# Motorisation.net
KiCad netlist of a schematic drawn in Altium Designer
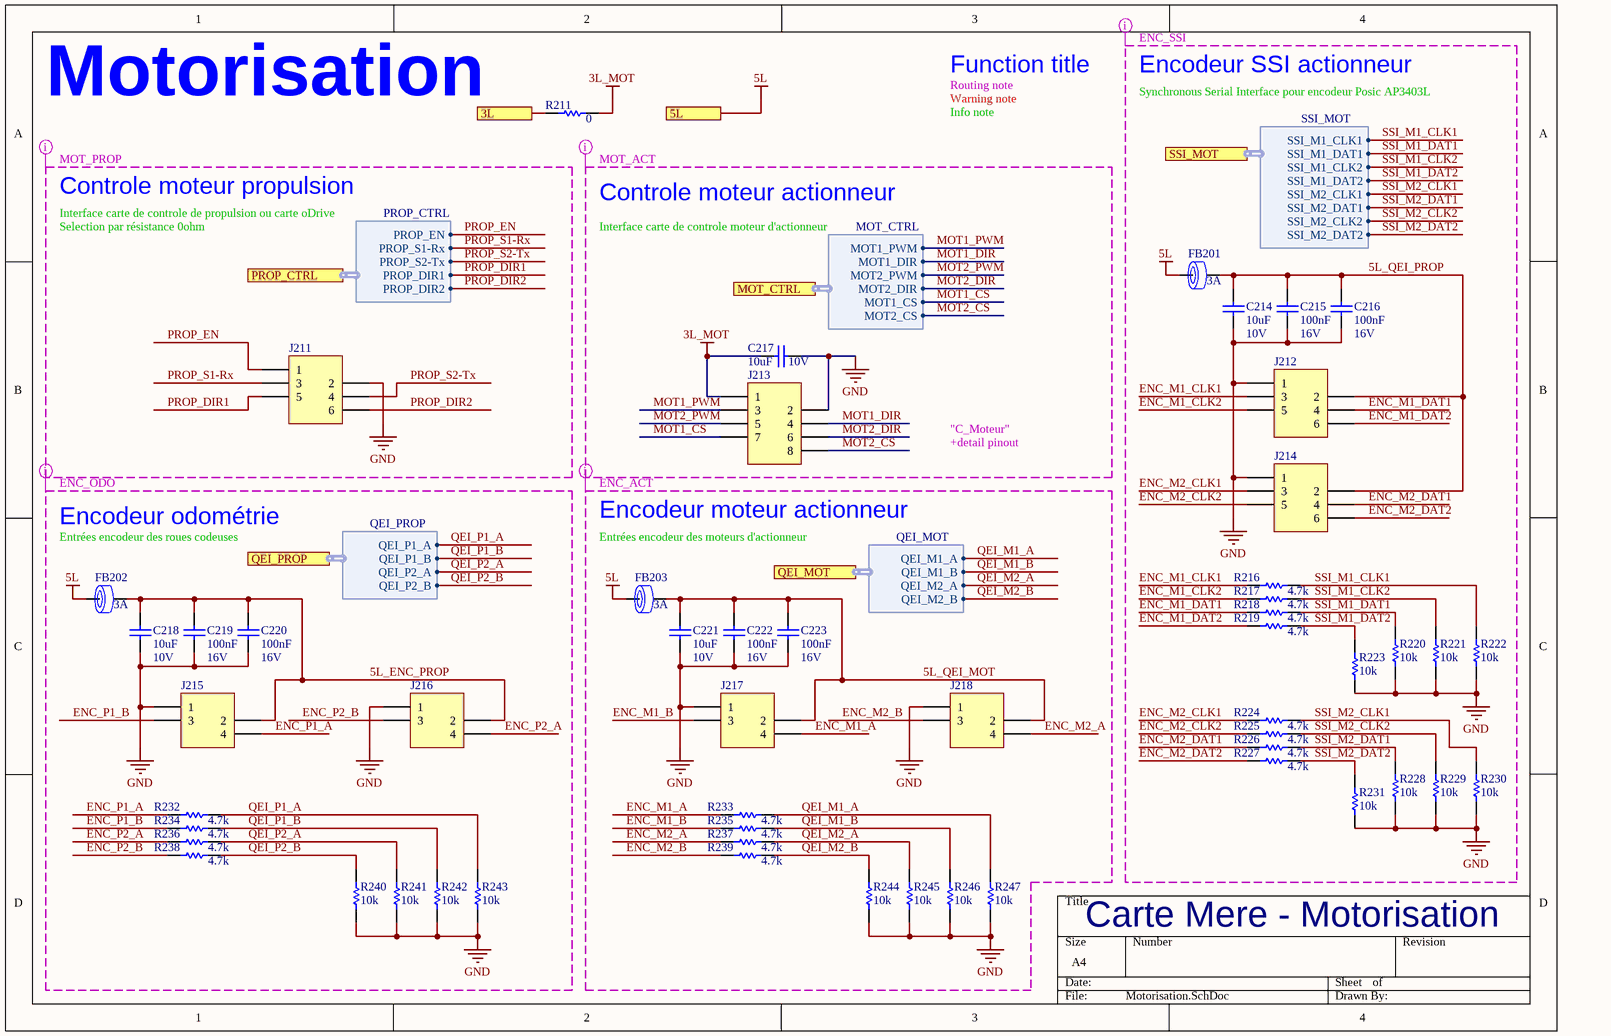
[diagram p0: Motorisation.SchDoc]

(export (version "E")
  (design (tool "Eeschema 10.0.6"))
  (components
    (comp (ref "C214")
      (value "10uF")
      (footprint "WCAP-CSGP_0805, 2x1.25x1.25")
      (description "CAP CER 10uF 10V X7R 0805")
      (fields
        (field (name "MANUFACTURER") "Wurth Elektronik")
        (field (name "MANUFACTURER PART NUMBER") "885012207026")
        (field (name "RATEDVOLTAGE") "10V")
      )
      (libsource (lib "Condensateur") (part "WCAP-CSGP, 885012207026"))
    )
    (comp (ref "C215")
      (value "100nF")
      (footprint "WCAP-CSGP_0402, 1x0.5x0.5")
      (description "CAP CER 100nF 16V X7R 0402")
      (fields
        (field (name "MANUFACTURER") "Wurth Elektronik")
        (field (name "MANUFACTURER PART NUMBER") "885012205037")
        (field (name "RATEDVOLTAGE") "16V")
      )
      (libsource (lib "Condensateur") (part "WCAP-CSGP, 885012205037"))
    )
    (comp (ref "C216")
      (value "100nF")
      (footprint "WCAP-CSGP_0402, 1x0.5x0.5")
      (description "CAP CER 100nF 16V X7R 0402")
      (fields
        (field (name "MANUFACTURER") "Wurth Elektronik")
        (field (name "MANUFACTURER PART NUMBER") "885012205037")
        (field (name "RATEDVOLTAGE") "16V")
      )
      (libsource (lib "Condensateur") (part "WCAP-CSGP, 885012205037"))
    )
    (comp (ref "C217")
      (value "10uF")
      (footprint "WCAP-CSGP_0805, 2x1.25x1.25")
      (description "CAP CER 10uF 10V X7R 0805")
      (fields
        (field (name "MANUFACTURER") "Wurth Elektronik")
        (field (name "MANUFACTURER PART NUMBER") "885012207026")
        (field (name "RATEDVOLTAGE") "10V")
      )
      (libsource (lib "Condensateur") (part "WCAP-CSGP, 885012207026"))
    )
    (comp (ref "C218")
      (value "10uF")
      (footprint "WCAP-CSGP_0805, 2x1.25x1.25")
      (description "CAP CER 10uF 10V X7R 0805")
      (fields
        (field (name "MANUFACTURER") "Wurth Elektronik")
        (field (name "MANUFACTURER PART NUMBER") "885012207026")
        (field (name "RATEDVOLTAGE") "10V")
      )
      (libsource (lib "Condensateur") (part "WCAP-CSGP, 885012207026"))
    )
    (comp (ref "C219")
      (value "100nF")
      (footprint "WCAP-CSGP_0402, 1x0.5x0.5")
      (description "CAP CER 100nF 16V X7R 0402")
      (fields
        (field (name "MANUFACTURER") "Wurth Elektronik")
        (field (name "MANUFACTURER PART NUMBER") "885012205037")
        (field (name "RATEDVOLTAGE") "16V")
      )
      (libsource (lib "Condensateur") (part "WCAP-CSGP, 885012205037"))
    )
    (comp (ref "C220")
      (value "100nF")
      (footprint "WCAP-CSGP_0402, 1x0.5x0.5")
      (description "CAP CER 100nF 16V X7R 0402")
      (fields
        (field (name "MANUFACTURER") "Wurth Elektronik")
        (field (name "MANUFACTURER PART NUMBER") "885012205037")
        (field (name "RATEDVOLTAGE") "16V")
      )
      (libsource (lib "Condensateur") (part "WCAP-CSGP, 885012205037"))
    )
    (comp (ref "C221")
      (value "10uF")
      (footprint "WCAP-CSGP_0805, 2x1.25x1.25")
      (description "CAP CER 10uF 10V X7R 0805")
      (fields
        (field (name "MANUFACTURER") "Wurth Elektronik")
        (field (name "MANUFACTURER PART NUMBER") "885012207026")
        (field (name "RATEDVOLTAGE") "10V")
      )
      (libsource (lib "Condensateur") (part "WCAP-CSGP, 885012207026"))
    )
    (comp (ref "C222")
      (value "100nF")
      (footprint "WCAP-CSGP_0402, 1x0.5x0.5")
      (description "CAP CER 100nF 16V X7R 0402")
      (fields
        (field (name "MANUFACTURER") "Wurth Elektronik")
        (field (name "MANUFACTURER PART NUMBER") "885012205037")
        (field (name "RATEDVOLTAGE") "16V")
      )
      (libsource (lib "Condensateur") (part "WCAP-CSGP, 885012205037"))
    )
    (comp (ref "C223")
      (value "100nF")
      (footprint "WCAP-CSGP_0402, 1x0.5x0.5")
      (description "CAP CER 100nF 16V X7R 0402")
      (fields
        (field (name "MANUFACTURER") "Wurth Elektronik")
        (field (name "MANUFACTURER PART NUMBER") "885012205037")
        (field (name "RATEDVOLTAGE") "16V")
      )
      (libsource (lib "Condensateur") (part "WCAP-CSGP, 885012205037"))
    )
    (comp (ref "FB201")
      (value "742792023")
      (footprint "WE-CBF_0805_High Current")
      (description "Ferrite Bead 120ohm 0805 3A")
      (fields (field (name "MANUFACTURER") "Wurth Elektronik") (field (name "RATEDCURRENT") "3A"))
      (libsource (lib "Inductance") (part "WE-CBF, 742792023"))
    )
    (comp (ref "FB202")
      (value "742792023")
      (footprint "WE-CBF_0805_High Current")
      (description "Ferrite Bead 120ohm 0805 3A")
      (fields (field (name "MANUFACTURER") "Wurth Elektronik") (field (name "RATEDCURRENT") "3A"))
      (libsource (lib "Inductance") (part "WE-CBF, 742792023"))
    )
    (comp (ref "FB203")
      (value "742792023")
      (footprint "WE-CBF_0805_High Current")
      (description "Ferrite Bead 120ohm 0805 3A")
      (fields (field (name "MANUFACTURER") "Wurth Elektronik") (field (name "RATEDCURRENT") "3A"))
      (libsource (lib "Inductance") (part "WE-CBF, 742792023"))
    )
    (comp (ref "J211")
      (value "690367280676")
      (footprint "690367280676")
      (description "WR-MM 6p Female SMT Connector with Polarization")
      (fields (field (name "MANUFACTURER") "Wurth Electronics Inc."))
      (libsource (lib "Connecteurs") (part "690367280676"))
    )
    (comp (ref "J212")
      (value "690367280676")
      (footprint "690367280676")
      (description "WR-MM 6p Female SMT Connector with Polarization")
      (fields (field (name "MANUFACTURER") "Wurth Electronics Inc."))
      (libsource (lib "Connecteurs") (part "690367280676"))
    )
    (comp (ref "J213")
      (value "690367280876")
      (footprint "690367280876")
      (description "WR-MM 8p Female SMT Connector with Polarization")
      (fields (field (name "MANUFACTURER") "Wurth Electronics Inc."))
      (libsource (lib "Connecteurs") (part "690367280876"))
    )
    (comp (ref "J214")
      (value "690367280676")
      (footprint "690367280676")
      (description "WR-MM 6p Female SMT Connector with Polarization")
      (fields (field (name "MANUFACTURER") "Wurth Electronics Inc."))
      (libsource (lib "Connecteurs") (part "690367280676"))
    )
    (comp (ref "J215")
      (value "690367280476")
      (footprint "690367280476")
      (description "WR-MM 4p Female SMT Connector with Polarization")
      (fields (field (name "MANUFACTURER") "Wurth Electronics Inc."))
      (libsource (lib "Connecteurs") (part "690367280476"))
    )
    (comp (ref "J216")
      (value "690367280476")
      (footprint "690367280476")
      (description "WR-MM 4p Female SMT Connector with Polarization")
      (fields (field (name "MANUFACTURER") "Wurth Electronics Inc."))
      (libsource (lib "Connecteurs") (part "690367280476"))
    )
    (comp (ref "J217")
      (value "690367280476")
      (footprint "690367280476")
      (description "WR-MM 4p Female SMT Connector with Polarization")
      (fields (field (name "MANUFACTURER") "Wurth Electronics Inc."))
      (libsource (lib "Connecteurs") (part "690367280476"))
    )
    (comp (ref "J218")
      (value "690367280476")
      (footprint "690367280476")
      (description "WR-MM 4p Female SMT Connector with Polarization")
      (fields (field (name "MANUFACTURER") "Wurth Electronics Inc."))
      (libsource (lib "Connecteurs") (part "690367280476"))
    )
    (comp (ref "R211")
      (value "0")
      (footprint "RESC1608X06N")
      (description "RES SMD 0 OHM 1% 1/10W 0603")
      (fields
        (field (name "MANUFACTURER") "Yageo")
        (field (name "MANUFACTURER PART NUMBER") "RC0603FR-070RL")
      )
      (libsource (lib "Resistance") (part "RC0603FR-070RL"))
    )
    (comp (ref "R216")
      (value "4.7k")
      (footprint "RESC1005X04N")
      (description "RES SMD 4K7 OHM 1% 1/16W 0402")
      (fields (field (name "POWER") "63mW") (field (name "MANUFACTURER") "Yageo"))
      (libsource (lib "Resistance") (part "RC0402FR-074K7L"))
    )
    (comp (ref "R217")
      (value "4.7k")
      (footprint "RESC1005X04N")
      (description "RES SMD 4K7 OHM 1% 1/16W 0402")
      (fields (field (name "POWER") "63mW") (field (name "MANUFACTURER") "Yageo"))
      (libsource (lib "Resistance") (part "RC0402FR-074K7L"))
    )
    (comp (ref "R218")
      (value "4.7k")
      (footprint "RESC1005X04N")
      (description "RES SMD 4K7 OHM 1% 1/16W 0402")
      (fields (field (name "POWER") "63mW") (field (name "MANUFACTURER") "Yageo"))
      (libsource (lib "Resistance") (part "RC0402FR-074K7L"))
    )
    (comp (ref "R219")
      (value "4.7k")
      (footprint "RESC1005X04N")
      (description "RES SMD 4K7 OHM 1% 1/16W 0402")
      (fields (field (name "POWER") "63mW") (field (name "MANUFACTURER") "Yageo"))
      (libsource (lib "Resistance") (part "RC0402FR-074K7L"))
    )
    (comp (ref "R220")
      (value "10k")
      (footprint "RESC1005X04N")
      (description "RES SMD 10K OHM 1% 1/16W 0402")
      (fields (field (name "POWER") "63mW") (field (name "MANUFACTURER") "Yageo"))
      (libsource (lib "Resistance") (part "RC0402FR-0710KL"))
    )
    (comp (ref "R221")
      (value "10k")
      (footprint "RESC1005X04N")
      (description "RES SMD 10K OHM 1% 1/16W 0402")
      (fields (field (name "POWER") "63mW") (field (name "MANUFACTURER") "Yageo"))
      (libsource (lib "Resistance") (part "RC0402FR-0710KL"))
    )
    (comp (ref "R222")
      (value "10k")
      (footprint "RESC1005X04N")
      (description "RES SMD 10K OHM 1% 1/16W 0402")
      (fields (field (name "POWER") "63mW") (field (name "MANUFACTURER") "Yageo"))
      (libsource (lib "Resistance") (part "RC0402FR-0710KL"))
    )
    (comp (ref "R223")
      (value "10k")
      (footprint "RESC1005X04N")
      (description "RES SMD 10K OHM 1% 1/16W 0402")
      (fields (field (name "POWER") "63mW") (field (name "MANUFACTURER") "Yageo"))
      (libsource (lib "Resistance") (part "RC0402FR-0710KL"))
    )
    (comp (ref "R224")
      (value "4.7k")
      (footprint "RESC1005X04N")
      (description "RES SMD 4K7 OHM 1% 1/16W 0402")
      (fields (field (name "POWER") "63mW") (field (name "MANUFACTURER") "Yageo"))
      (libsource (lib "Resistance") (part "RC0402FR-074K7L"))
    )
    (comp (ref "R225")
      (value "4.7k")
      (footprint "RESC1005X04N")
      (description "RES SMD 4K7 OHM 1% 1/16W 0402")
      (fields (field (name "POWER") "63mW") (field (name "MANUFACTURER") "Yageo"))
      (libsource (lib "Resistance") (part "RC0402FR-074K7L"))
    )
    (comp (ref "R226")
      (value "4.7k")
      (footprint "RESC1005X04N")
      (description "RES SMD 4K7 OHM 1% 1/16W 0402")
      (fields (field (name "POWER") "63mW") (field (name "MANUFACTURER") "Yageo"))
      (libsource (lib "Resistance") (part "RC0402FR-074K7L"))
    )
    (comp (ref "R227")
      (value "4.7k")
      (footprint "RESC1005X04N")
      (description "RES SMD 4K7 OHM 1% 1/16W 0402")
      (fields (field (name "POWER") "63mW") (field (name "MANUFACTURER") "Yageo"))
      (libsource (lib "Resistance") (part "RC0402FR-074K7L"))
    )
    (comp (ref "R228")
      (value "10k")
      (footprint "RESC1005X04N")
      (description "RES SMD 10K OHM 1% 1/16W 0402")
      (fields (field (name "POWER") "63mW") (field (name "MANUFACTURER") "Yageo"))
      (libsource (lib "Resistance") (part "RC0402FR-0710KL"))
    )
    (comp (ref "R229")
      (value "10k")
      (footprint "RESC1005X04N")
      (description "RES SMD 10K OHM 1% 1/16W 0402")
      (fields (field (name "POWER") "63mW") (field (name "MANUFACTURER") "Yageo"))
      (libsource (lib "Resistance") (part "RC0402FR-0710KL"))
    )
    (comp (ref "R230")
      (value "10k")
      (footprint "RESC1005X04N")
      (description "RES SMD 10K OHM 1% 1/16W 0402")
      (fields (field (name "POWER") "63mW") (field (name "MANUFACTURER") "Yageo"))
      (libsource (lib "Resistance") (part "RC0402FR-0710KL"))
    )
    (comp (ref "R231")
      (value "10k")
      (footprint "RESC1005X04N")
      (description "RES SMD 10K OHM 1% 1/16W 0402")
      (fields (field (name "POWER") "63mW") (field (name "MANUFACTURER") "Yageo"))
      (libsource (lib "Resistance") (part "RC0402FR-0710KL"))
    )
    (comp (ref "R232")
      (value "4.7k")
      (footprint "RESC1005X04N")
      (description "RES SMD 4K7 OHM 1% 1/16W 0402")
      (fields (field (name "POWER") "63mW") (field (name "MANUFACTURER") "Yageo"))
      (libsource (lib "Resistance") (part "RC0402FR-074K7L"))
    )
    (comp (ref "R233")
      (value "4.7k")
      (footprint "RESC1005X04N")
      (description "RES SMD 4K7 OHM 1% 1/16W 0402")
      (fields (field (name "POWER") "63mW") (field (name "MANUFACTURER") "Yageo"))
      (libsource (lib "Resistance") (part "RC0402FR-074K7L"))
    )
    (comp (ref "R234")
      (value "4.7k")
      (footprint "RESC1005X04N")
      (description "RES SMD 4K7 OHM 1% 1/16W 0402")
      (fields (field (name "POWER") "63mW") (field (name "MANUFACTURER") "Yageo"))
      (libsource (lib "Resistance") (part "RC0402FR-074K7L"))
    )
    (comp (ref "R235")
      (value "4.7k")
      (footprint "RESC1005X04N")
      (description "RES SMD 4K7 OHM 1% 1/16W 0402")
      (fields (field (name "POWER") "63mW") (field (name "MANUFACTURER") "Yageo"))
      (libsource (lib "Resistance") (part "RC0402FR-074K7L"))
    )
    (comp (ref "R236")
      (value "4.7k")
      (footprint "RESC1005X04N")
      (description "RES SMD 4K7 OHM 1% 1/16W 0402")
      (fields (field (name "POWER") "63mW") (field (name "MANUFACTURER") "Yageo"))
      (libsource (lib "Resistance") (part "RC0402FR-074K7L"))
    )
    (comp (ref "R237")
      (value "4.7k")
      (footprint "RESC1005X04N")
      (description "RES SMD 4K7 OHM 1% 1/16W 0402")
      (fields (field (name "POWER") "63mW") (field (name "MANUFACTURER") "Yageo"))
      (libsource (lib "Resistance") (part "RC0402FR-074K7L"))
    )
    (comp (ref "R238")
      (value "4.7k")
      (footprint "RESC1005X04N")
      (description "RES SMD 4K7 OHM 1% 1/16W 0402")
      (fields (field (name "POWER") "63mW") (field (name "MANUFACTURER") "Yageo"))
      (libsource (lib "Resistance") (part "RC0402FR-074K7L"))
    )
    (comp (ref "R239")
      (value "4.7k")
      (footprint "RESC1005X04N")
      (description "RES SMD 4K7 OHM 1% 1/16W 0402")
      (fields (field (name "POWER") "63mW") (field (name "MANUFACTURER") "Yageo"))
      (libsource (lib "Resistance") (part "RC0402FR-074K7L"))
    )
    (comp (ref "R240")
      (value "10k")
      (footprint "RESC1005X04N")
      (description "RES SMD 10K OHM 1% 1/16W 0402")
      (fields (field (name "POWER") "63mW") (field (name "MANUFACTURER") "Yageo"))
      (libsource (lib "Resistance") (part "RC0402FR-0710KL"))
    )
    (comp (ref "R241")
      (value "10k")
      (footprint "RESC1005X04N")
      (description "RES SMD 10K OHM 1% 1/16W 0402")
      (fields (field (name "POWER") "63mW") (field (name "MANUFACTURER") "Yageo"))
      (libsource (lib "Resistance") (part "RC0402FR-0710KL"))
    )
    (comp (ref "R242")
      (value "10k")
      (footprint "RESC1005X04N")
      (description "RES SMD 10K OHM 1% 1/16W 0402")
      (fields (field (name "POWER") "63mW") (field (name "MANUFACTURER") "Yageo"))
      (libsource (lib "Resistance") (part "RC0402FR-0710KL"))
    )
    (comp (ref "R243")
      (value "10k")
      (footprint "RESC1005X04N")
      (description "RES SMD 10K OHM 1% 1/16W 0402")
      (fields (field (name "POWER") "63mW") (field (name "MANUFACTURER") "Yageo"))
      (libsource (lib "Resistance") (part "RC0402FR-0710KL"))
    )
    (comp (ref "R244")
      (value "10k")
      (footprint "RESC1005X04N")
      (description "RES SMD 10K OHM 1% 1/16W 0402")
      (fields (field (name "POWER") "63mW") (field (name "MANUFACTURER") "Yageo"))
      (libsource (lib "Resistance") (part "RC0402FR-0710KL"))
    )
    (comp (ref "R245")
      (value "10k")
      (footprint "RESC1005X04N")
      (description "RES SMD 10K OHM 1% 1/16W 0402")
      (fields (field (name "POWER") "63mW") (field (name "MANUFACTURER") "Yageo"))
      (libsource (lib "Resistance") (part "RC0402FR-0710KL"))
    )
    (comp (ref "R246")
      (value "10k")
      (footprint "RESC1005X04N")
      (description "RES SMD 10K OHM 1% 1/16W 0402")
      (fields (field (name "POWER") "63mW") (field (name "MANUFACTURER") "Yageo"))
      (libsource (lib "Resistance") (part "RC0402FR-0710KL"))
    )
    (comp (ref "R247")
      (value "10k")
      (footprint "RESC1005X04N")
      (description "RES SMD 10K OHM 1% 1/16W 0402")
      (fields (field (name "POWER") "63mW") (field (name "MANUFACTURER") "Yageo"))
      (libsource (lib "Resistance") (part "RC0402FR-0710KL"))
    )
  )
  (nets
    (net (code "6") (name "/3L") (class "Default")
      (node (ref "R211") (pin "1") (pinfunction "1_1") (pintype "passive"))
    )
    (net (code "7") (name "/5L_ENC_PROP") (class "Default")
      (node (ref "C218") (pin "1") (pinfunction "1_1") (pintype "passive"))
      (node (ref "C219") (pin "1") (pinfunction "1_1") (pintype "passive"))
      (node (ref "C220") (pin "1") (pinfunction "1_1") (pintype "passive"))
      (node (ref "FB202") (pin "2") (pinfunction "2_2") (pintype "passive"))
      (node (ref "J215") (pin "2") (pinfunction "2_2") (pintype "passive"))
      (node (ref "J216") (pin "2") (pinfunction "2_2") (pintype "passive"))
    )
    (net (code "8") (name "/5L_QEI_MOT") (class "Default")
      (node (ref "C221") (pin "1") (pinfunction "1_1") (pintype "passive"))
      (node (ref "C222") (pin "1") (pinfunction "1_1") (pintype "passive"))
      (node (ref "C223") (pin "1") (pinfunction "1_1") (pintype "passive"))
      (node (ref "FB203") (pin "2") (pinfunction "2_2") (pintype "passive"))
      (node (ref "J217") (pin "2") (pinfunction "2_2") (pintype "passive"))
      (node (ref "J218") (pin "2") (pinfunction "2_2") (pintype "passive"))
    )
    (net (code "9") (name "/5L_QEI_PROP") (class "Default")
      (node (ref "C214") (pin "1") (pinfunction "1_1") (pintype "passive"))
      (node (ref "C215") (pin "1") (pinfunction "1_1") (pintype "passive"))
      (node (ref "C216") (pin "1") (pinfunction "1_1") (pintype "passive"))
      (node (ref "FB201") (pin "2") (pinfunction "2_2") (pintype "passive"))
      (node (ref "J212") (pin "2") (pinfunction "2_2") (pintype "passive"))
      (node (ref "J214") (pin "2") (pinfunction "2_2") (pintype "passive"))
    )
    (net (code "10") (name "/ENC_M1_A") (class "Default")
      (node (ref "J217") (pin "4") (pinfunction "4_4") (pintype "passive"))
      (node (ref "R233") (pin "1") (pinfunction "1_1") (pintype "passive"))
    )
    (net (code "11") (name "/ENC_M1_B") (class "Default")
      (node (ref "J217") (pin "3") (pinfunction "3_3") (pintype "passive"))
      (node (ref "R235") (pin "1") (pinfunction "1_1") (pintype "passive"))
    )
    (net (code "12") (name "/ENC_M1_CLK1") (class "Default")
      (node (ref "J212") (pin "3") (pinfunction "3_3") (pintype "passive"))
      (node (ref "R216") (pin "1") (pinfunction "1_1") (pintype "passive"))
    )
    (net (code "13") (name "/ENC_M1_CLK2") (class "Default")
      (node (ref "J212") (pin "5") (pinfunction "5_5") (pintype "passive"))
      (node (ref "R217") (pin "1") (pinfunction "1_1") (pintype "passive"))
    )
    (net (code "14") (name "/ENC_M1_DAT1") (class "Default")
      (node (ref "J212") (pin "4") (pinfunction "4_4") (pintype "passive"))
      (node (ref "R218") (pin "1") (pinfunction "1_1") (pintype "passive"))
    )
    (net (code "15") (name "/ENC_M1_DAT2") (class "Default")
      (node (ref "J212") (pin "6") (pinfunction "6_6") (pintype "passive"))
      (node (ref "R219") (pin "1") (pinfunction "1_1") (pintype "passive"))
    )
    (net (code "16") (name "/ENC_M2_A") (class "Default")
      (node (ref "J218") (pin "4") (pinfunction "4_4") (pintype "passive"))
      (node (ref "R237") (pin "1") (pinfunction "1_1") (pintype "passive"))
    )
    (net (code "17") (name "/ENC_M2_B") (class "Default")
      (node (ref "J218") (pin "3") (pinfunction "3_3") (pintype "passive"))
      (node (ref "R239") (pin "1") (pinfunction "1_1") (pintype "passive"))
    )
    (net (code "18") (name "/ENC_M2_CLK1") (class "Default")
      (node (ref "J214") (pin "3") (pinfunction "3_3") (pintype "passive"))
      (node (ref "R224") (pin "1") (pinfunction "1_1") (pintype "passive"))
    )
    (net (code "19") (name "/ENC_M2_CLK2") (class "Default")
      (node (ref "J214") (pin "5") (pinfunction "5_5") (pintype "passive"))
      (node (ref "R225") (pin "1") (pinfunction "1_1") (pintype "passive"))
    )
    (net (code "20") (name "/ENC_M2_DAT1") (class "Default")
      (node (ref "J214") (pin "4") (pinfunction "4_4") (pintype "passive"))
      (node (ref "R226") (pin "1") (pinfunction "1_1") (pintype "passive"))
    )
    (net (code "21") (name "/ENC_M2_DAT2") (class "Default")
      (node (ref "J214") (pin "6") (pinfunction "6_6") (pintype "passive"))
      (node (ref "R227") (pin "1") (pinfunction "1_1") (pintype "passive"))
    )
    (net (code "22") (name "/ENC_P1_A") (class "Default")
      (node (ref "J215") (pin "4") (pinfunction "4_4") (pintype "passive"))
      (node (ref "R232") (pin "1") (pinfunction "1_1") (pintype "passive"))
    )
    (net (code "23") (name "/ENC_P1_B") (class "Default")
      (node (ref "J215") (pin "3") (pinfunction "3_3") (pintype "passive"))
      (node (ref "R234") (pin "1") (pinfunction "1_1") (pintype "passive"))
    )
    (net (code "24") (name "/ENC_P2_A") (class "Default")
      (node (ref "J216") (pin "4") (pinfunction "4_4") (pintype "passive"))
      (node (ref "R236") (pin "1") (pinfunction "1_1") (pintype "passive"))
    )
    (net (code "25") (name "/ENC_P2_B") (class "Default")
      (node (ref "J216") (pin "3") (pinfunction "3_3") (pintype "passive"))
      (node (ref "R238") (pin "1") (pinfunction "1_1") (pintype "passive"))
    )
    (net (code "26") (name "/MOT1_CS") (class "Default")
      (node (ref "J213") (pin "7") (pinfunction "7_7") (pintype "passive"))
    )
    (net (code "27") (name "/MOT1_DIR") (class "Default")
      (node (ref "J213") (pin "4") (pinfunction "4_4") (pintype "passive"))
    )
    (net (code "28") (name "/MOT1_PWM") (class "Default")
      (node (ref "J213") (pin "3") (pinfunction "3_3") (pintype "passive"))
    )
    (net (code "29") (name "/MOT2_CS") (class "Default")
      (node (ref "J213") (pin "8") (pinfunction "8_8") (pintype "passive"))
    )
    (net (code "30") (name "/MOT2_DIR") (class "Default")
      (node (ref "J213") (pin "6") (pinfunction "6_6") (pintype "passive"))
    )
    (net (code "31") (name "/MOT2_PWM") (class "Default")
      (node (ref "J213") (pin "5") (pinfunction "5_5") (pintype "passive"))
    )
    (net (code "32") (name "/PROP_DIR1") (class "Default")
      (node (ref "J211") (pin "5") (pinfunction "5_5") (pintype "passive"))
    )
    (net (code "33") (name "/PROP_DIR2") (class "Default")
      (node (ref "J211") (pin "6") (pinfunction "6_6") (pintype "passive"))
    )
    (net (code "34") (name "/PROP_EN") (class "Default")
      (node (ref "J211") (pin "1") (pinfunction "1_1") (pintype "passive"))
    )
    (net (code "35") (name "/PROP_S1-Rx") (class "Default")
      (node (ref "J211") (pin "3") (pinfunction "3_3") (pintype "passive"))
    )
    (net (code "36") (name "/PROP_S2-Tx") (class "Default")
      (node (ref "J211") (pin "4") (pinfunction "4_4") (pintype "passive"))
    )
    (net (code "37") (name "/QEI_M1_A") (class "Default")
      (node (ref "R233") (pin "2") (pinfunction "2_2") (pintype "passive"))
      (node (ref "R247") (pin "2") (pinfunction "2_2") (pintype "passive"))
    )
    (net (code "38") (name "/QEI_M1_B") (class "Default")
      (node (ref "R235") (pin "2") (pinfunction "2_2") (pintype "passive"))
      (node (ref "R246") (pin "2") (pinfunction "2_2") (pintype "passive"))
    )
    (net (code "39") (name "/QEI_M2_A") (class "Default")
      (node (ref "R237") (pin "2") (pinfunction "2_2") (pintype "passive"))
      (node (ref "R245") (pin "2") (pinfunction "2_2") (pintype "passive"))
    )
    (net (code "40") (name "/QEI_M2_B") (class "Default")
      (node (ref "R239") (pin "2") (pinfunction "2_2") (pintype "passive"))
      (node (ref "R244") (pin "2") (pinfunction "2_2") (pintype "passive"))
    )
    (net (code "41") (name "/QEI_P1_A") (class "Default")
      (node (ref "R232") (pin "2") (pinfunction "2_2") (pintype "passive"))
      (node (ref "R243") (pin "2") (pinfunction "2_2") (pintype "passive"))
    )
    (net (code "42") (name "/QEI_P1_B") (class "Default")
      (node (ref "R234") (pin "2") (pinfunction "2_2") (pintype "passive"))
      (node (ref "R242") (pin "2") (pinfunction "2_2") (pintype "passive"))
    )
    (net (code "43") (name "/QEI_P2_A") (class "Default")
      (node (ref "R236") (pin "2") (pinfunction "2_2") (pintype "passive"))
      (node (ref "R241") (pin "2") (pinfunction "2_2") (pintype "passive"))
    )
    (net (code "44") (name "/QEI_P2_B") (class "Default")
      (node (ref "R238") (pin "2") (pinfunction "2_2") (pintype "passive"))
      (node (ref "R240") (pin "2") (pinfunction "2_2") (pintype "passive"))
    )
    (net (code "45") (name "/SSI_M1_CLK1") (class "Default")
      (node (ref "R216") (pin "2") (pinfunction "2_2") (pintype "passive"))
      (node (ref "R222") (pin "2") (pinfunction "2_2") (pintype "passive"))
    )
    (net (code "46") (name "/SSI_M1_CLK2") (class "Default")
      (node (ref "R217") (pin "2") (pinfunction "2_2") (pintype "passive"))
      (node (ref "R221") (pin "2") (pinfunction "2_2") (pintype "passive"))
    )
    (net (code "47") (name "/SSI_M1_DAT1") (class "Default")
      (node (ref "R218") (pin "2") (pinfunction "2_2") (pintype "passive"))
      (node (ref "R220") (pin "2") (pinfunction "2_2") (pintype "passive"))
    )
    (net (code "48") (name "/SSI_M1_DAT2") (class "Default")
      (node (ref "R219") (pin "2") (pinfunction "2_2") (pintype "passive"))
      (node (ref "R223") (pin "2") (pinfunction "2_2") (pintype "passive"))
    )
    (net (code "49") (name "/SSI_M2_CLK1") (class "Default")
      (node (ref "R224") (pin "2") (pinfunction "2_2") (pintype "passive"))
      (node (ref "R230") (pin "2") (pinfunction "2_2") (pintype "passive"))
    )
    (net (code "50") (name "/SSI_M2_CLK2") (class "Default")
      (node (ref "R225") (pin "2") (pinfunction "2_2") (pintype "passive"))
      (node (ref "R229") (pin "2") (pinfunction "2_2") (pintype "passive"))
    )
    (net (code "51") (name "/SSI_M2_DAT1") (class "Default")
      (node (ref "R226") (pin "2") (pinfunction "2_2") (pintype "passive"))
      (node (ref "R228") (pin "2") (pinfunction "2_2") (pintype "passive"))
    )
    (net (code "52") (name "/SSI_M2_DAT2") (class "Default")
      (node (ref "R227") (pin "2") (pinfunction "2_2") (pintype "passive"))
      (node (ref "R231") (pin "2") (pinfunction "2_2") (pintype "passive"))
    )
    (net (code "58") (name "3L_MOT") (class "Default")
      (node (ref "C217") (pin "1") (pinfunction "1_1") (pintype "passive"))
      (node (ref "J213") (pin "1") (pinfunction "1_1") (pintype "passive"))
      (node (ref "R211") (pin "2") (pinfunction "2_2") (pintype "passive"))
    )
    (net (code "59") (name "5L") (class "Default")
      (node (ref "FB201") (pin "1") (pinfunction "1_1") (pintype "passive"))
      (node (ref "FB202") (pin "1") (pinfunction "1_1") (pintype "passive"))
      (node (ref "FB203") (pin "1") (pinfunction "1_1") (pintype "passive"))
    )
    (net (code "60") (name "GND") (class "Default")
      (node (ref "C214") (pin "2") (pinfunction "2_2") (pintype "passive"))
      (node (ref "C215") (pin "2") (pinfunction "2_2") (pintype "passive"))
      (node (ref "C216") (pin "2") (pinfunction "2_2") (pintype "passive"))
      (node (ref "C217") (pin "2") (pinfunction "2_2") (pintype "passive"))
      (node (ref "C218") (pin "2") (pinfunction "2_2") (pintype "passive"))
      (node (ref "C219") (pin "2") (pinfunction "2_2") (pintype "passive"))
      (node (ref "C220") (pin "2") (pinfunction "2_2") (pintype "passive"))
      (node (ref "C221") (pin "2") (pinfunction "2_2") (pintype "passive"))
      (node (ref "C222") (pin "2") (pinfunction "2_2") (pintype "passive"))
      (node (ref "C223") (pin "2") (pinfunction "2_2") (pintype "passive"))
      (node (ref "J211") (pin "2") (pinfunction "2_2") (pintype "passive"))
      (node (ref "J212") (pin "1") (pinfunction "1_1") (pintype "passive"))
      (node (ref "J213") (pin "2") (pinfunction "2_2") (pintype "passive"))
      (node (ref "J214") (pin "1") (pinfunction "1_1") (pintype "passive"))
      (node (ref "J215") (pin "1") (pinfunction "1_1") (pintype "passive"))
      (node (ref "J216") (pin "1") (pinfunction "1_1") (pintype "passive"))
      (node (ref "J217") (pin "1") (pinfunction "1_1") (pintype "passive"))
      (node (ref "J218") (pin "1") (pinfunction "1_1") (pintype "passive"))
      (node (ref "R220") (pin "1") (pinfunction "1_1") (pintype "passive"))
      (node (ref "R221") (pin "1") (pinfunction "1_1") (pintype "passive"))
      (node (ref "R222") (pin "1") (pinfunction "1_1") (pintype "passive"))
      (node (ref "R223") (pin "1") (pinfunction "1_1") (pintype "passive"))
      (node (ref "R228") (pin "1") (pinfunction "1_1") (pintype "passive"))
      (node (ref "R229") (pin "1") (pinfunction "1_1") (pintype "passive"))
      (node (ref "R230") (pin "1") (pinfunction "1_1") (pintype "passive"))
      (node (ref "R231") (pin "1") (pinfunction "1_1") (pintype "passive"))
      (node (ref "R240") (pin "1") (pinfunction "1_1") (pintype "passive"))
      (node (ref "R241") (pin "1") (pinfunction "1_1") (pintype "passive"))
      (node (ref "R242") (pin "1") (pinfunction "1_1") (pintype "passive"))
      (node (ref "R243") (pin "1") (pinfunction "1_1") (pintype "passive"))
      (node (ref "R244") (pin "1") (pinfunction "1_1") (pintype "passive"))
      (node (ref "R245") (pin "1") (pinfunction "1_1") (pintype "passive"))
      (node (ref "R246") (pin "1") (pinfunction "1_1") (pintype "passive"))
      (node (ref "R247") (pin "1") (pinfunction "1_1") (pintype "passive"))
    )
  )
)
